# DAQBOARD.net
KiCad netlist of a schematic drawn in EAGLE
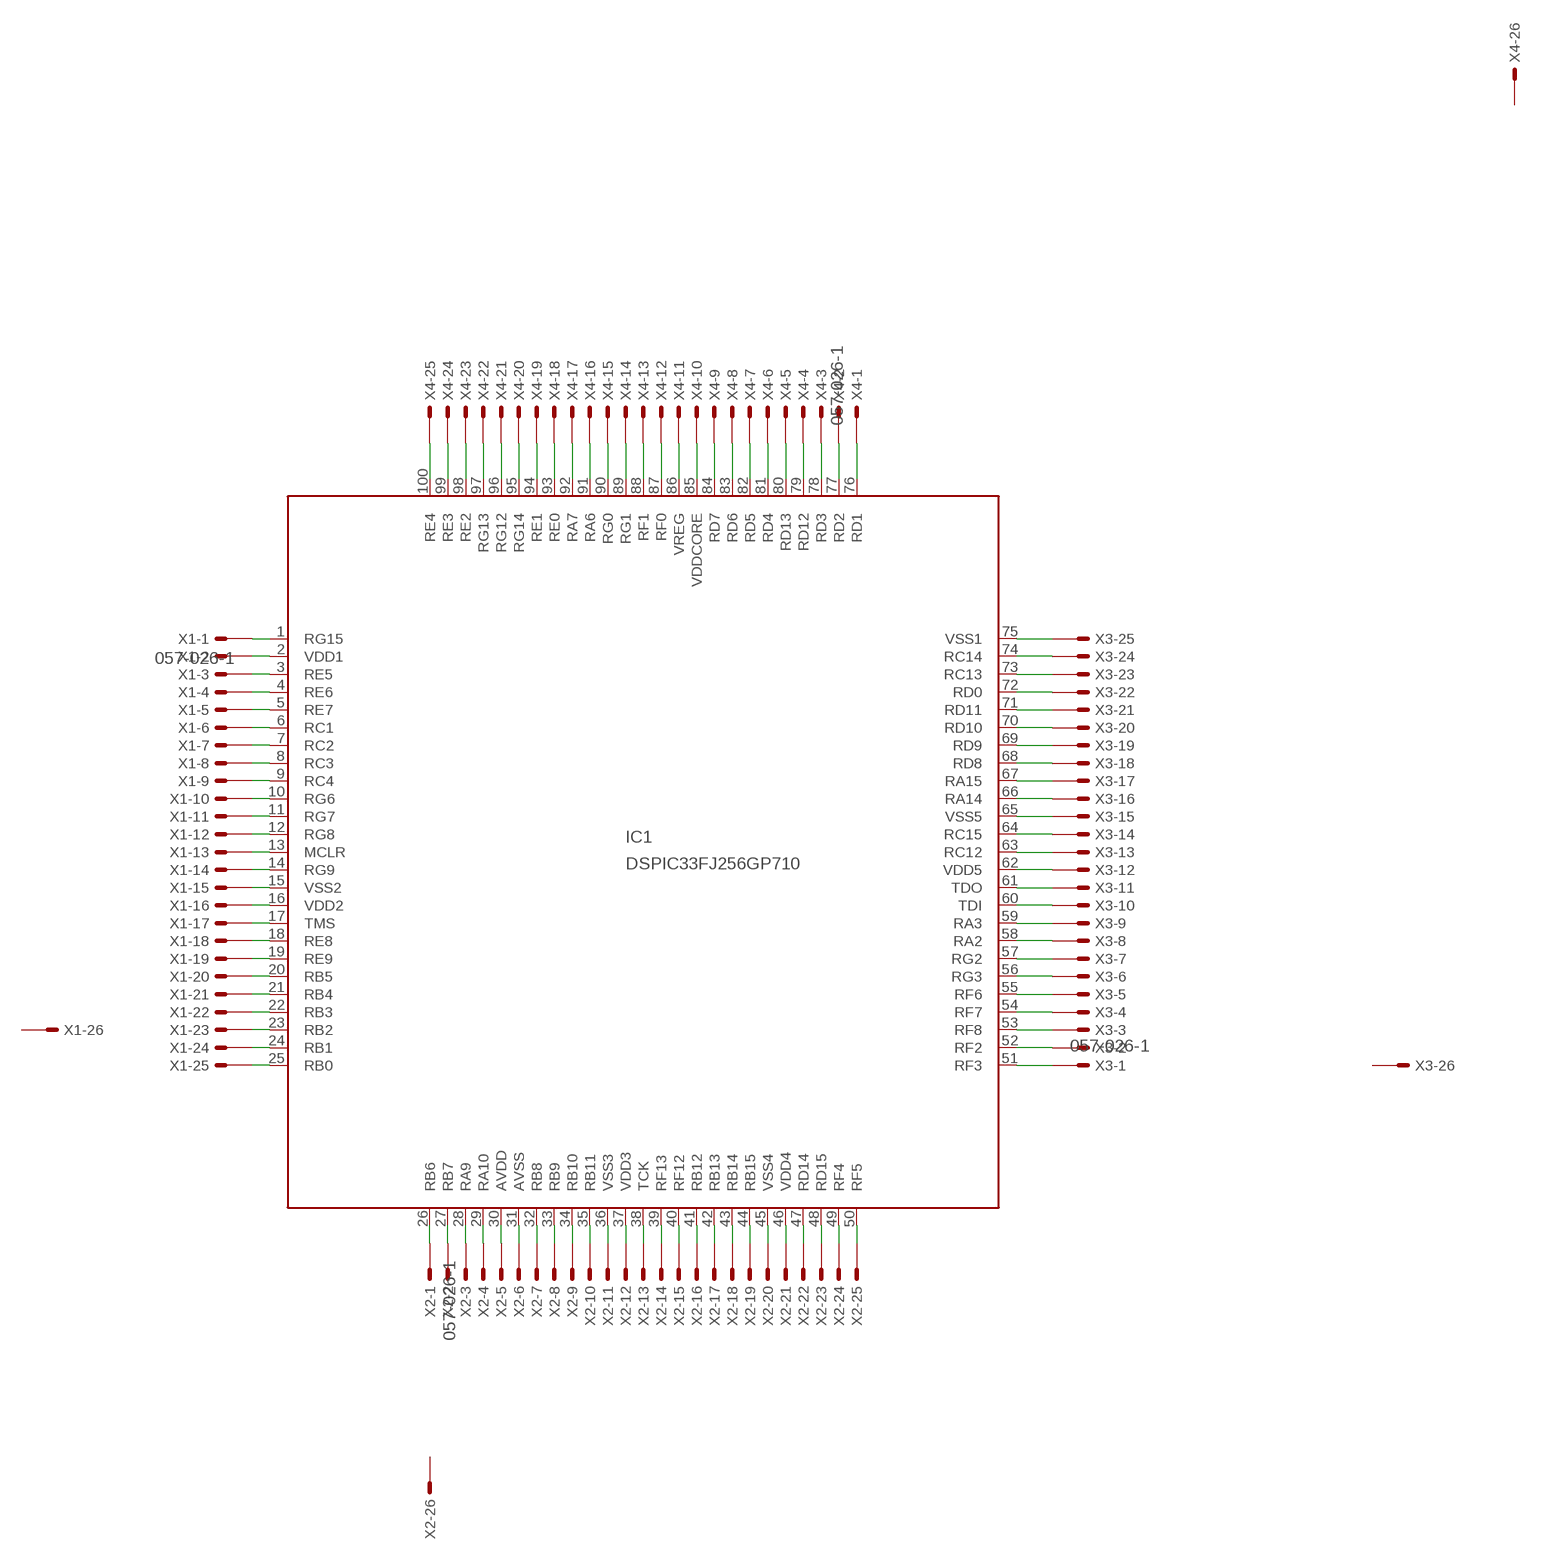
[diagram p0: schematic, sheet 1]

(export (version "E")
  (design (tool "Eeschema 10.0.6"))
  (components
    (comp (ref "IC1")
      (value "DSPIC33FJ256GP710")
      (footprint "eagle-import:TQFP100-12X12")
      (libsource (lib "eagle-import") (part "DSPIC33FJ256GP710"))
    )
    (comp (ref "X1")
      (value "057-026-1")
      (footprint "eagle-import:057-026-1")
      (libsource (lib "eagle-import") (part "057-026-1"))
    )
    (comp (ref "X2")
      (value "057-026-1")
      (footprint "eagle-import:057-026-1")
      (libsource (lib "eagle-import") (part "057-026-1"))
    )
    (comp (ref "X3")
      (value "057-026-1")
      (footprint "eagle-import:057-026-1")
      (libsource (lib "eagle-import") (part "057-026-1"))
    )
    (comp (ref "X4")
      (value "057-026-1")
      (footprint "eagle-import:057-026-1")
      (libsource (lib "eagle-import") (part "057-026-1"))
    )
  )
  (nets
    (net (code "1") (name "Net-(IC1-AVDD)") (class "Default")
      (node (ref "IC1") (pin "30") (pinfunction "AVDD_30") (pintype "power_in"))
      (node (ref "X2") (pin "5") (pinfunction "S_5") (pintype "passive"))
    )
    (net (code "2") (name "Net-(IC1-AVSS)") (class "Default")
      (node (ref "IC1") (pin "31") (pinfunction "AVSS_31") (pintype "power_in"))
      (node (ref "X2") (pin "6") (pinfunction "S_6") (pintype "passive"))
    )
    (net (code "3") (name "Net-(IC1-MCLR)") (class "Default")
      (node (ref "IC1") (pin "13") (pinfunction "MCLR_13") (pintype "bidirectional"))
      (node (ref "X1") (pin "13") (pinfunction "S_13") (pintype "passive"))
    )
    (net (code "4") (name "Net-(IC1-RA2)") (class "Default")
      (node (ref "IC1") (pin "58") (pinfunction "RA2_58") (pintype "bidirectional"))
      (node (ref "X3") (pin "8") (pinfunction "S_8") (pintype "passive"))
    )
    (net (code "5") (name "Net-(IC1-RA3)") (class "Default")
      (node (ref "IC1") (pin "59") (pinfunction "RA3_59") (pintype "bidirectional"))
      (node (ref "X3") (pin "9") (pinfunction "S_9") (pintype "passive"))
    )
    (net (code "6") (name "Net-(IC1-RA6)") (class "Default")
      (node (ref "IC1") (pin "91") (pinfunction "RA6_91") (pintype "bidirectional"))
      (node (ref "X4") (pin "16") (pinfunction "S_16") (pintype "passive"))
    )
    (net (code "7") (name "Net-(IC1-RA7)") (class "Default")
      (node (ref "IC1") (pin "92") (pinfunction "RA7_92") (pintype "bidirectional"))
      (node (ref "X4") (pin "17") (pinfunction "S_17") (pintype "passive"))
    )
    (net (code "8") (name "Net-(IC1-RA9)") (class "Default")
      (node (ref "IC1") (pin "28") (pinfunction "RA9_28") (pintype "bidirectional"))
      (node (ref "X2") (pin "3") (pinfunction "S_3") (pintype "passive"))
    )
    (net (code "9") (name "Net-(IC1-RA10)") (class "Default")
      (node (ref "IC1") (pin "29") (pinfunction "RA10_29") (pintype "bidirectional"))
      (node (ref "X2") (pin "4") (pinfunction "S_4") (pintype "passive"))
    )
    (net (code "10") (name "Net-(IC1-RA14)") (class "Default")
      (node (ref "IC1") (pin "66") (pinfunction "RA14_66") (pintype "bidirectional"))
      (node (ref "X3") (pin "16") (pinfunction "S_16") (pintype "passive"))
    )
    (net (code "11") (name "Net-(IC1-RA15)") (class "Default")
      (node (ref "IC1") (pin "67") (pinfunction "RA15_67") (pintype "bidirectional"))
      (node (ref "X3") (pin "17") (pinfunction "S_17") (pintype "passive"))
    )
    (net (code "12") (name "Net-(IC1-RB0)") (class "Default")
      (node (ref "IC1") (pin "25") (pinfunction "RB0_25") (pintype "bidirectional"))
      (node (ref "X1") (pin "25") (pinfunction "S_25") (pintype "passive"))
    )
    (net (code "13") (name "Net-(IC1-RB1)") (class "Default")
      (node (ref "IC1") (pin "24") (pinfunction "RB1_24") (pintype "bidirectional"))
      (node (ref "X1") (pin "24") (pinfunction "S_24") (pintype "passive"))
    )
    (net (code "14") (name "Net-(IC1-RB2)") (class "Default")
      (node (ref "IC1") (pin "23") (pinfunction "RB2_23") (pintype "bidirectional"))
      (node (ref "X1") (pin "23") (pinfunction "S_23") (pintype "passive"))
    )
    (net (code "15") (name "Net-(IC1-RB3)") (class "Default")
      (node (ref "IC1") (pin "22") (pinfunction "RB3_22") (pintype "bidirectional"))
      (node (ref "X1") (pin "22") (pinfunction "S_22") (pintype "passive"))
    )
    (net (code "16") (name "Net-(IC1-RB4)") (class "Default")
      (node (ref "IC1") (pin "21") (pinfunction "RB4_21") (pintype "bidirectional"))
      (node (ref "X1") (pin "21") (pinfunction "S_21") (pintype "passive"))
    )
    (net (code "17") (name "Net-(IC1-RB5)") (class "Default")
      (node (ref "IC1") (pin "20") (pinfunction "RB5_20") (pintype "bidirectional"))
      (node (ref "X1") (pin "20") (pinfunction "S_20") (pintype "passive"))
    )
    (net (code "18") (name "Net-(IC1-RB6)") (class "Default")
      (node (ref "IC1") (pin "26") (pinfunction "RB6_26") (pintype "bidirectional"))
      (node (ref "X2") (pin "1") (pinfunction "S_1") (pintype "passive"))
    )
    (net (code "19") (name "Net-(IC1-RB7)") (class "Default")
      (node (ref "IC1") (pin "27") (pinfunction "RB7_27") (pintype "bidirectional"))
      (node (ref "X2") (pin "2") (pinfunction "S_2") (pintype "passive"))
    )
    (net (code "20") (name "Net-(IC1-RB8)") (class "Default")
      (node (ref "IC1") (pin "32") (pinfunction "RB8_32") (pintype "bidirectional"))
      (node (ref "X2") (pin "7") (pinfunction "S_7") (pintype "passive"))
    )
    (net (code "21") (name "Net-(IC1-RB9)") (class "Default")
      (node (ref "IC1") (pin "33") (pinfunction "RB9_33") (pintype "bidirectional"))
      (node (ref "X2") (pin "8") (pinfunction "S_8") (pintype "passive"))
    )
    (net (code "22") (name "Net-(IC1-RB10)") (class "Default")
      (node (ref "IC1") (pin "34") (pinfunction "RB10_34") (pintype "bidirectional"))
      (node (ref "X2") (pin "9") (pinfunction "S_9") (pintype "passive"))
    )
    (net (code "23") (name "Net-(IC1-RB11)") (class "Default")
      (node (ref "IC1") (pin "35") (pinfunction "RB11_35") (pintype "bidirectional"))
      (node (ref "X2") (pin "10") (pinfunction "S_10") (pintype "passive"))
    )
    (net (code "24") (name "Net-(IC1-RB12)") (class "Default")
      (node (ref "IC1") (pin "41") (pinfunction "RB12_41") (pintype "bidirectional"))
      (node (ref "X2") (pin "16") (pinfunction "S_16") (pintype "passive"))
    )
    (net (code "25") (name "Net-(IC1-RB13)") (class "Default")
      (node (ref "IC1") (pin "42") (pinfunction "RB13_42") (pintype "bidirectional"))
      (node (ref "X2") (pin "17") (pinfunction "S_17") (pintype "passive"))
    )
    (net (code "26") (name "Net-(IC1-RB14)") (class "Default")
      (node (ref "IC1") (pin "43") (pinfunction "RB14_43") (pintype "bidirectional"))
      (node (ref "X2") (pin "18") (pinfunction "S_18") (pintype "passive"))
    )
    (net (code "27") (name "Net-(IC1-RB15)") (class "Default")
      (node (ref "IC1") (pin "44") (pinfunction "RB15_44") (pintype "bidirectional"))
      (node (ref "X2") (pin "19") (pinfunction "S_19") (pintype "passive"))
    )
    (net (code "28") (name "Net-(IC1-RC1)") (class "Default")
      (node (ref "IC1") (pin "6") (pinfunction "RC1_6") (pintype "bidirectional"))
      (node (ref "X1") (pin "6") (pinfunction "S_6") (pintype "passive"))
    )
    (net (code "29") (name "Net-(IC1-RC2)") (class "Default")
      (node (ref "IC1") (pin "7") (pinfunction "RC2_7") (pintype "bidirectional"))
      (node (ref "X1") (pin "7") (pinfunction "S_7") (pintype "passive"))
    )
    (net (code "30") (name "Net-(IC1-RC3)") (class "Default")
      (node (ref "IC1") (pin "8") (pinfunction "RC3_8") (pintype "bidirectional"))
      (node (ref "X1") (pin "8") (pinfunction "S_8") (pintype "passive"))
    )
    (net (code "31") (name "Net-(IC1-RC4)") (class "Default")
      (node (ref "IC1") (pin "9") (pinfunction "RC4_9") (pintype "bidirectional"))
      (node (ref "X1") (pin "9") (pinfunction "S_9") (pintype "passive"))
    )
    (net (code "32") (name "Net-(IC1-RC12)") (class "Default")
      (node (ref "IC1") (pin "63") (pinfunction "RC12_63") (pintype "bidirectional"))
      (node (ref "X3") (pin "13") (pinfunction "S_13") (pintype "passive"))
    )
    (net (code "33") (name "Net-(IC1-RC13)") (class "Default")
      (node (ref "IC1") (pin "73") (pinfunction "RC13_73") (pintype "bidirectional"))
      (node (ref "X3") (pin "23") (pinfunction "S_23") (pintype "passive"))
    )
    (net (code "34") (name "Net-(IC1-RC14)") (class "Default")
      (node (ref "IC1") (pin "74") (pinfunction "RC14_74") (pintype "bidirectional"))
      (node (ref "X3") (pin "24") (pinfunction "S_24") (pintype "passive"))
    )
    (net (code "35") (name "Net-(IC1-RC15)") (class "Default")
      (node (ref "IC1") (pin "64") (pinfunction "RC15_64") (pintype "bidirectional"))
      (node (ref "X3") (pin "14") (pinfunction "S_14") (pintype "passive"))
    )
    (net (code "36") (name "Net-(IC1-RD0)") (class "Default")
      (node (ref "IC1") (pin "72") (pinfunction "RD0_72") (pintype "bidirectional"))
      (node (ref "X3") (pin "22") (pinfunction "S_22") (pintype "passive"))
    )
    (net (code "37") (name "Net-(IC1-RD1)") (class "Default")
      (node (ref "IC1") (pin "76") (pinfunction "RD1_76") (pintype "bidirectional"))
      (node (ref "X4") (pin "1") (pinfunction "S_1") (pintype "passive"))
    )
    (net (code "38") (name "Net-(IC1-RD2)") (class "Default")
      (node (ref "IC1") (pin "77") (pinfunction "RD2_77") (pintype "bidirectional"))
      (node (ref "X4") (pin "2") (pinfunction "S_2") (pintype "passive"))
    )
    (net (code "39") (name "Net-(IC1-RD3)") (class "Default")
      (node (ref "IC1") (pin "78") (pinfunction "RD3_78") (pintype "bidirectional"))
      (node (ref "X4") (pin "3") (pinfunction "S_3") (pintype "passive"))
    )
    (net (code "40") (name "Net-(IC1-RD4)") (class "Default")
      (node (ref "IC1") (pin "81") (pinfunction "RD4_81") (pintype "bidirectional"))
      (node (ref "X4") (pin "6") (pinfunction "S_6") (pintype "passive"))
    )
    (net (code "41") (name "Net-(IC1-RD5)") (class "Default")
      (node (ref "IC1") (pin "82") (pinfunction "RD5_82") (pintype "bidirectional"))
      (node (ref "X4") (pin "7") (pinfunction "S_7") (pintype "passive"))
    )
    (net (code "42") (name "Net-(IC1-RD6)") (class "Default")
      (node (ref "IC1") (pin "83") (pinfunction "RD6_83") (pintype "bidirectional"))
      (node (ref "X4") (pin "8") (pinfunction "S_8") (pintype "passive"))
    )
    (net (code "43") (name "Net-(IC1-RD7)") (class "Default")
      (node (ref "IC1") (pin "84") (pinfunction "RD7_84") (pintype "bidirectional"))
      (node (ref "X4") (pin "9") (pinfunction "S_9") (pintype "passive"))
    )
    (net (code "44") (name "Net-(IC1-RD8)") (class "Default")
      (node (ref "IC1") (pin "68") (pinfunction "RD8_68") (pintype "bidirectional"))
      (node (ref "X3") (pin "18") (pinfunction "S_18") (pintype "passive"))
    )
    (net (code "45") (name "Net-(IC1-RD9)") (class "Default")
      (node (ref "IC1") (pin "69") (pinfunction "RD9_69") (pintype "bidirectional"))
      (node (ref "X3") (pin "19") (pinfunction "S_19") (pintype "passive"))
    )
    (net (code "46") (name "Net-(IC1-RD10)") (class "Default")
      (node (ref "IC1") (pin "70") (pinfunction "RD10_70") (pintype "bidirectional"))
      (node (ref "X3") (pin "20") (pinfunction "S_20") (pintype "passive"))
    )
    (net (code "47") (name "Net-(IC1-RD11)") (class "Default")
      (node (ref "IC1") (pin "71") (pinfunction "RD11_71") (pintype "bidirectional"))
      (node (ref "X3") (pin "21") (pinfunction "S_21") (pintype "passive"))
    )
    (net (code "48") (name "Net-(IC1-RD12)") (class "Default")
      (node (ref "IC1") (pin "79") (pinfunction "RD12_79") (pintype "bidirectional"))
      (node (ref "X4") (pin "4") (pinfunction "S_4") (pintype "passive"))
    )
    (net (code "49") (name "Net-(IC1-RD13)") (class "Default")
      (node (ref "IC1") (pin "80") (pinfunction "RD13_80") (pintype "bidirectional"))
      (node (ref "X4") (pin "5") (pinfunction "S_5") (pintype "passive"))
    )
    (net (code "50") (name "Net-(IC1-RD14)") (class "Default")
      (node (ref "IC1") (pin "47") (pinfunction "RD14_47") (pintype "bidirectional"))
      (node (ref "X2") (pin "22") (pinfunction "S_22") (pintype "passive"))
    )
    (net (code "51") (name "Net-(IC1-RD15)") (class "Default")
      (node (ref "IC1") (pin "48") (pinfunction "RD15_48") (pintype "bidirectional"))
      (node (ref "X2") (pin "23") (pinfunction "S_23") (pintype "passive"))
    )
    (net (code "52") (name "Net-(IC1-RE0)") (class "Default")
      (node (ref "IC1") (pin "93") (pinfunction "RE0_93") (pintype "bidirectional"))
      (node (ref "X4") (pin "18") (pinfunction "S_18") (pintype "passive"))
    )
    (net (code "53") (name "Net-(IC1-RE1)") (class "Default")
      (node (ref "IC1") (pin "94") (pinfunction "RE1_94") (pintype "bidirectional"))
      (node (ref "X4") (pin "19") (pinfunction "S_19") (pintype "passive"))
    )
    (net (code "54") (name "Net-(IC1-RE2)") (class "Default")
      (node (ref "IC1") (pin "98") (pinfunction "RE2_98") (pintype "bidirectional"))
      (node (ref "X4") (pin "23") (pinfunction "S_23") (pintype "passive"))
    )
    (net (code "55") (name "Net-(IC1-RE3)") (class "Default")
      (node (ref "IC1") (pin "99") (pinfunction "RE3_99") (pintype "bidirectional"))
      (node (ref "X4") (pin "24") (pinfunction "S_24") (pintype "passive"))
    )
    (net (code "56") (name "Net-(IC1-RE4)") (class "Default")
      (node (ref "IC1") (pin "100") (pinfunction "RE4_100") (pintype "bidirectional"))
      (node (ref "X4") (pin "25") (pinfunction "S_25") (pintype "passive"))
    )
    (net (code "57") (name "Net-(IC1-RE5)") (class "Default")
      (node (ref "IC1") (pin "3") (pinfunction "RE5_3") (pintype "bidirectional"))
      (node (ref "X1") (pin "3") (pinfunction "S_3") (pintype "passive"))
    )
    (net (code "58") (name "Net-(IC1-RE6)") (class "Default")
      (node (ref "IC1") (pin "4") (pinfunction "RE6_4") (pintype "bidirectional"))
      (node (ref "X1") (pin "4") (pinfunction "S_4") (pintype "passive"))
    )
    (net (code "59") (name "Net-(IC1-RE7)") (class "Default")
      (node (ref "IC1") (pin "5") (pinfunction "RE7_5") (pintype "bidirectional"))
      (node (ref "X1") (pin "5") (pinfunction "S_5") (pintype "passive"))
    )
    (net (code "60") (name "Net-(IC1-RE8)") (class "Default")
      (node (ref "IC1") (pin "18") (pinfunction "RE8_18") (pintype "bidirectional"))
      (node (ref "X1") (pin "18") (pinfunction "S_18") (pintype "passive"))
    )
    (net (code "61") (name "Net-(IC1-RE9)") (class "Default")
      (node (ref "IC1") (pin "19") (pinfunction "RE9_19") (pintype "bidirectional"))
      (node (ref "X1") (pin "19") (pinfunction "S_19") (pintype "passive"))
    )
    (net (code "62") (name "Net-(IC1-RF0)") (class "Default")
      (node (ref "IC1") (pin "87") (pinfunction "RF0_87") (pintype "bidirectional"))
      (node (ref "X4") (pin "12") (pinfunction "S_12") (pintype "passive"))
    )
    (net (code "63") (name "Net-(IC1-RF1)") (class "Default")
      (node (ref "IC1") (pin "88") (pinfunction "RF1_88") (pintype "bidirectional"))
      (node (ref "X4") (pin "13") (pinfunction "S_13") (pintype "passive"))
    )
    (net (code "64") (name "Net-(IC1-RF2)") (class "Default")
      (node (ref "IC1") (pin "52") (pinfunction "RF2_52") (pintype "bidirectional"))
      (node (ref "X3") (pin "2") (pinfunction "S_2") (pintype "passive"))
    )
    (net (code "65") (name "Net-(IC1-RF3)") (class "Default")
      (node (ref "IC1") (pin "51") (pinfunction "RF3_51") (pintype "bidirectional"))
      (node (ref "X3") (pin "1") (pinfunction "S_1") (pintype "passive"))
    )
    (net (code "66") (name "Net-(IC1-RF4)") (class "Default")
      (node (ref "IC1") (pin "49") (pinfunction "RF4_49") (pintype "bidirectional"))
      (node (ref "X2") (pin "24") (pinfunction "S_24") (pintype "passive"))
    )
    (net (code "67") (name "Net-(IC1-RF5)") (class "Default")
      (node (ref "IC1") (pin "50") (pinfunction "RF5_50") (pintype "bidirectional"))
      (node (ref "X2") (pin "25") (pinfunction "S_25") (pintype "passive"))
    )
    (net (code "68") (name "Net-(IC1-RF6)") (class "Default")
      (node (ref "IC1") (pin "55") (pinfunction "RF6_55") (pintype "bidirectional"))
      (node (ref "X3") (pin "5") (pinfunction "S_5") (pintype "passive"))
    )
    (net (code "69") (name "Net-(IC1-RF7)") (class "Default")
      (node (ref "IC1") (pin "54") (pinfunction "RF7_54") (pintype "bidirectional"))
      (node (ref "X3") (pin "4") (pinfunction "S_4") (pintype "passive"))
    )
    (net (code "70") (name "Net-(IC1-RF8)") (class "Default")
      (node (ref "IC1") (pin "53") (pinfunction "RF8_53") (pintype "bidirectional"))
      (node (ref "X3") (pin "3") (pinfunction "S_3") (pintype "passive"))
    )
    (net (code "71") (name "Net-(IC1-RF12)") (class "Default")
      (node (ref "IC1") (pin "40") (pinfunction "RF12_40") (pintype "bidirectional"))
      (node (ref "X2") (pin "15") (pinfunction "S_15") (pintype "passive"))
    )
    (net (code "72") (name "Net-(IC1-RF13)") (class "Default")
      (node (ref "IC1") (pin "39") (pinfunction "RF13_39") (pintype "bidirectional"))
      (node (ref "X2") (pin "14") (pinfunction "S_14") (pintype "passive"))
    )
    (net (code "73") (name "Net-(IC1-RG0)") (class "Default")
      (node (ref "IC1") (pin "90") (pinfunction "RG0_90") (pintype "bidirectional"))
      (node (ref "X4") (pin "15") (pinfunction "S_15") (pintype "passive"))
    )
    (net (code "74") (name "Net-(IC1-RG1)") (class "Default")
      (node (ref "IC1") (pin "89") (pinfunction "RG1_89") (pintype "bidirectional"))
      (node (ref "X4") (pin "14") (pinfunction "S_14") (pintype "passive"))
    )
    (net (code "75") (name "Net-(IC1-RG2)") (class "Default")
      (node (ref "IC1") (pin "57") (pinfunction "RG2_57") (pintype "bidirectional"))
      (node (ref "X3") (pin "7") (pinfunction "S_7") (pintype "passive"))
    )
    (net (code "76") (name "Net-(IC1-RG3)") (class "Default")
      (node (ref "IC1") (pin "56") (pinfunction "RG3_56") (pintype "bidirectional"))
      (node (ref "X3") (pin "6") (pinfunction "S_6") (pintype "passive"))
    )
    (net (code "77") (name "Net-(IC1-RG6)") (class "Default")
      (node (ref "IC1") (pin "10") (pinfunction "RG6_10") (pintype "bidirectional"))
      (node (ref "X1") (pin "10") (pinfunction "S_10") (pintype "passive"))
    )
    (net (code "78") (name "Net-(IC1-RG7)") (class "Default")
      (node (ref "IC1") (pin "11") (pinfunction "RG7_11") (pintype "bidirectional"))
      (node (ref "X1") (pin "11") (pinfunction "S_11") (pintype "passive"))
    )
    (net (code "79") (name "Net-(IC1-RG8)") (class "Default")
      (node (ref "IC1") (pin "12") (pinfunction "RG8_12") (pintype "bidirectional"))
      (node (ref "X1") (pin "12") (pinfunction "S_12") (pintype "passive"))
    )
    (net (code "80") (name "Net-(IC1-RG9)") (class "Default")
      (node (ref "IC1") (pin "14") (pinfunction "RG9_14") (pintype "bidirectional"))
      (node (ref "X1") (pin "14") (pinfunction "S_14") (pintype "passive"))
    )
    (net (code "81") (name "Net-(IC1-RG12)") (class "Default")
      (node (ref "IC1") (pin "96") (pinfunction "RG12_96") (pintype "bidirectional"))
      (node (ref "X4") (pin "21") (pinfunction "S_21") (pintype "passive"))
    )
    (net (code "82") (name "Net-(IC1-RG13)") (class "Default")
      (node (ref "IC1") (pin "97") (pinfunction "RG13_97") (pintype "bidirectional"))
      (node (ref "X4") (pin "22") (pinfunction "S_22") (pintype "passive"))
    )
    (net (code "83") (name "Net-(IC1-RG14)") (class "Default")
      (node (ref "IC1") (pin "95") (pinfunction "RG14_95") (pintype "bidirectional"))
      (node (ref "X4") (pin "20") (pinfunction "S_20") (pintype "passive"))
    )
    (net (code "84") (name "Net-(IC1-RG15)") (class "Default")
      (node (ref "IC1") (pin "1") (pinfunction "RG15_1") (pintype "bidirectional"))
      (node (ref "X1") (pin "1") (pinfunction "S_1") (pintype "passive"))
    )
    (net (code "85") (name "Net-(IC1-TCK)") (class "Default")
      (node (ref "IC1") (pin "38") (pinfunction "TCK_38") (pintype "input"))
      (node (ref "X2") (pin "13") (pinfunction "S_13") (pintype "passive"))
    )
    (net (code "86") (name "Net-(IC1-TDI)") (class "Default")
      (node (ref "IC1") (pin "60") (pinfunction "TDI_60") (pintype "input"))
      (node (ref "X3") (pin "10") (pinfunction "S_10") (pintype "passive"))
    )
    (net (code "87") (name "Net-(IC1-TDO)") (class "Default")
      (node (ref "IC1") (pin "61") (pinfunction "TDO_61") (pintype "output"))
      (node (ref "X3") (pin "11") (pinfunction "S_11") (pintype "passive"))
    )
    (net (code "88") (name "Net-(IC1-TMS)") (class "Default")
      (node (ref "IC1") (pin "17") (pinfunction "TMS_17") (pintype "input"))
      (node (ref "X1") (pin "17") (pinfunction "S_17") (pintype "passive"))
    )
    (net (code "89") (name "Net-(IC1-VDD1)") (class "Default")
      (node (ref "IC1") (pin "2") (pinfunction "VDD1_2") (pintype "power_in"))
      (node (ref "X1") (pin "2") (pinfunction "S_2") (pintype "passive"))
    )
    (net (code "90") (name "Net-(IC1-VDD2)") (class "Default")
      (node (ref "IC1") (pin "16") (pinfunction "VDD2_16") (pintype "power_in"))
      (node (ref "X1") (pin "16") (pinfunction "S_16") (pintype "passive"))
    )
    (net (code "91") (name "Net-(IC1-VDD3)") (class "Default")
      (node (ref "IC1") (pin "37") (pinfunction "VDD3_37") (pintype "power_in"))
      (node (ref "X2") (pin "12") (pinfunction "S_12") (pintype "passive"))
    )
    (net (code "92") (name "Net-(IC1-VDD4)") (class "Default")
      (node (ref "IC1") (pin "46") (pinfunction "VDD4_46") (pintype "power_in"))
      (node (ref "X2") (pin "21") (pinfunction "S_21") (pintype "passive"))
    )
    (net (code "93") (name "Net-(IC1-VDD5)") (class "Default")
      (node (ref "IC1") (pin "62") (pinfunction "VDD5_62") (pintype "power_in"))
      (node (ref "X3") (pin "12") (pinfunction "S_12") (pintype "passive"))
    )
    (net (code "94") (name "Net-(IC1-VDDCORE)") (class "Default")
      (node (ref "IC1") (pin "85") (pinfunction "VDDCORE_85") (pintype "power_in"))
      (node (ref "X4") (pin "10") (pinfunction "S_10") (pintype "passive"))
    )
    (net (code "95") (name "Net-(IC1-VREG)") (class "Default")
      (node (ref "IC1") (pin "86") (pinfunction "VREG_86") (pintype "passive"))
      (node (ref "X4") (pin "11") (pinfunction "S_11") (pintype "passive"))
    )
    (net (code "96") (name "Net-(IC1-VSS1)") (class "Default")
      (node (ref "IC1") (pin "75") (pinfunction "VSS1_75") (pintype "power_in"))
      (node (ref "X3") (pin "25") (pinfunction "S_25") (pintype "passive"))
    )
    (net (code "97") (name "Net-(IC1-VSS2)") (class "Default")
      (node (ref "IC1") (pin "15") (pinfunction "VSS2_15") (pintype "power_in"))
      (node (ref "X1") (pin "15") (pinfunction "S_15") (pintype "passive"))
    )
    (net (code "98") (name "Net-(IC1-VSS3)") (class "Default")
      (node (ref "IC1") (pin "36") (pinfunction "VSS3_36") (pintype "power_in"))
      (node (ref "X2") (pin "11") (pinfunction "S_11") (pintype "passive"))
    )
    (net (code "99") (name "Net-(IC1-VSS4)") (class "Default")
      (node (ref "IC1") (pin "45") (pinfunction "VSS4_45") (pintype "power_in"))
      (node (ref "X2") (pin "20") (pinfunction "S_20") (pintype "passive"))
    )
    (net (code "100") (name "Net-(IC1-VSS5)") (class "Default")
      (node (ref "IC1") (pin "65") (pinfunction "VSS5_65") (pintype "power_in"))
      (node (ref "X3") (pin "15") (pinfunction "S_15") (pintype "passive"))
    )
    (net (code "101") (name "unconnected-(X1S-S-Pad26)") (class "Default")
      (node (ref "X1") (pin "26") (pinfunction "S_26") (pintype "passive"))
    )
    (net (code "102") (name "unconnected-(X2S-S-Pad26)") (class "Default")
      (node (ref "X2") (pin "26") (pinfunction "S_26") (pintype "passive"))
    )
    (net (code "103") (name "unconnected-(X3S-S-Pad26)") (class "Default")
      (node (ref "X3") (pin "26") (pinfunction "S_26") (pintype "passive"))
    )
    (net (code "104") (name "unconnected-(X4S-S-Pad26)") (class "Default")
      (node (ref "X4") (pin "26") (pinfunction "S_26") (pintype "passive"))
    )
  )
)
